# interacto.net
KiCad netlist of a schematic drawn in EAGLE
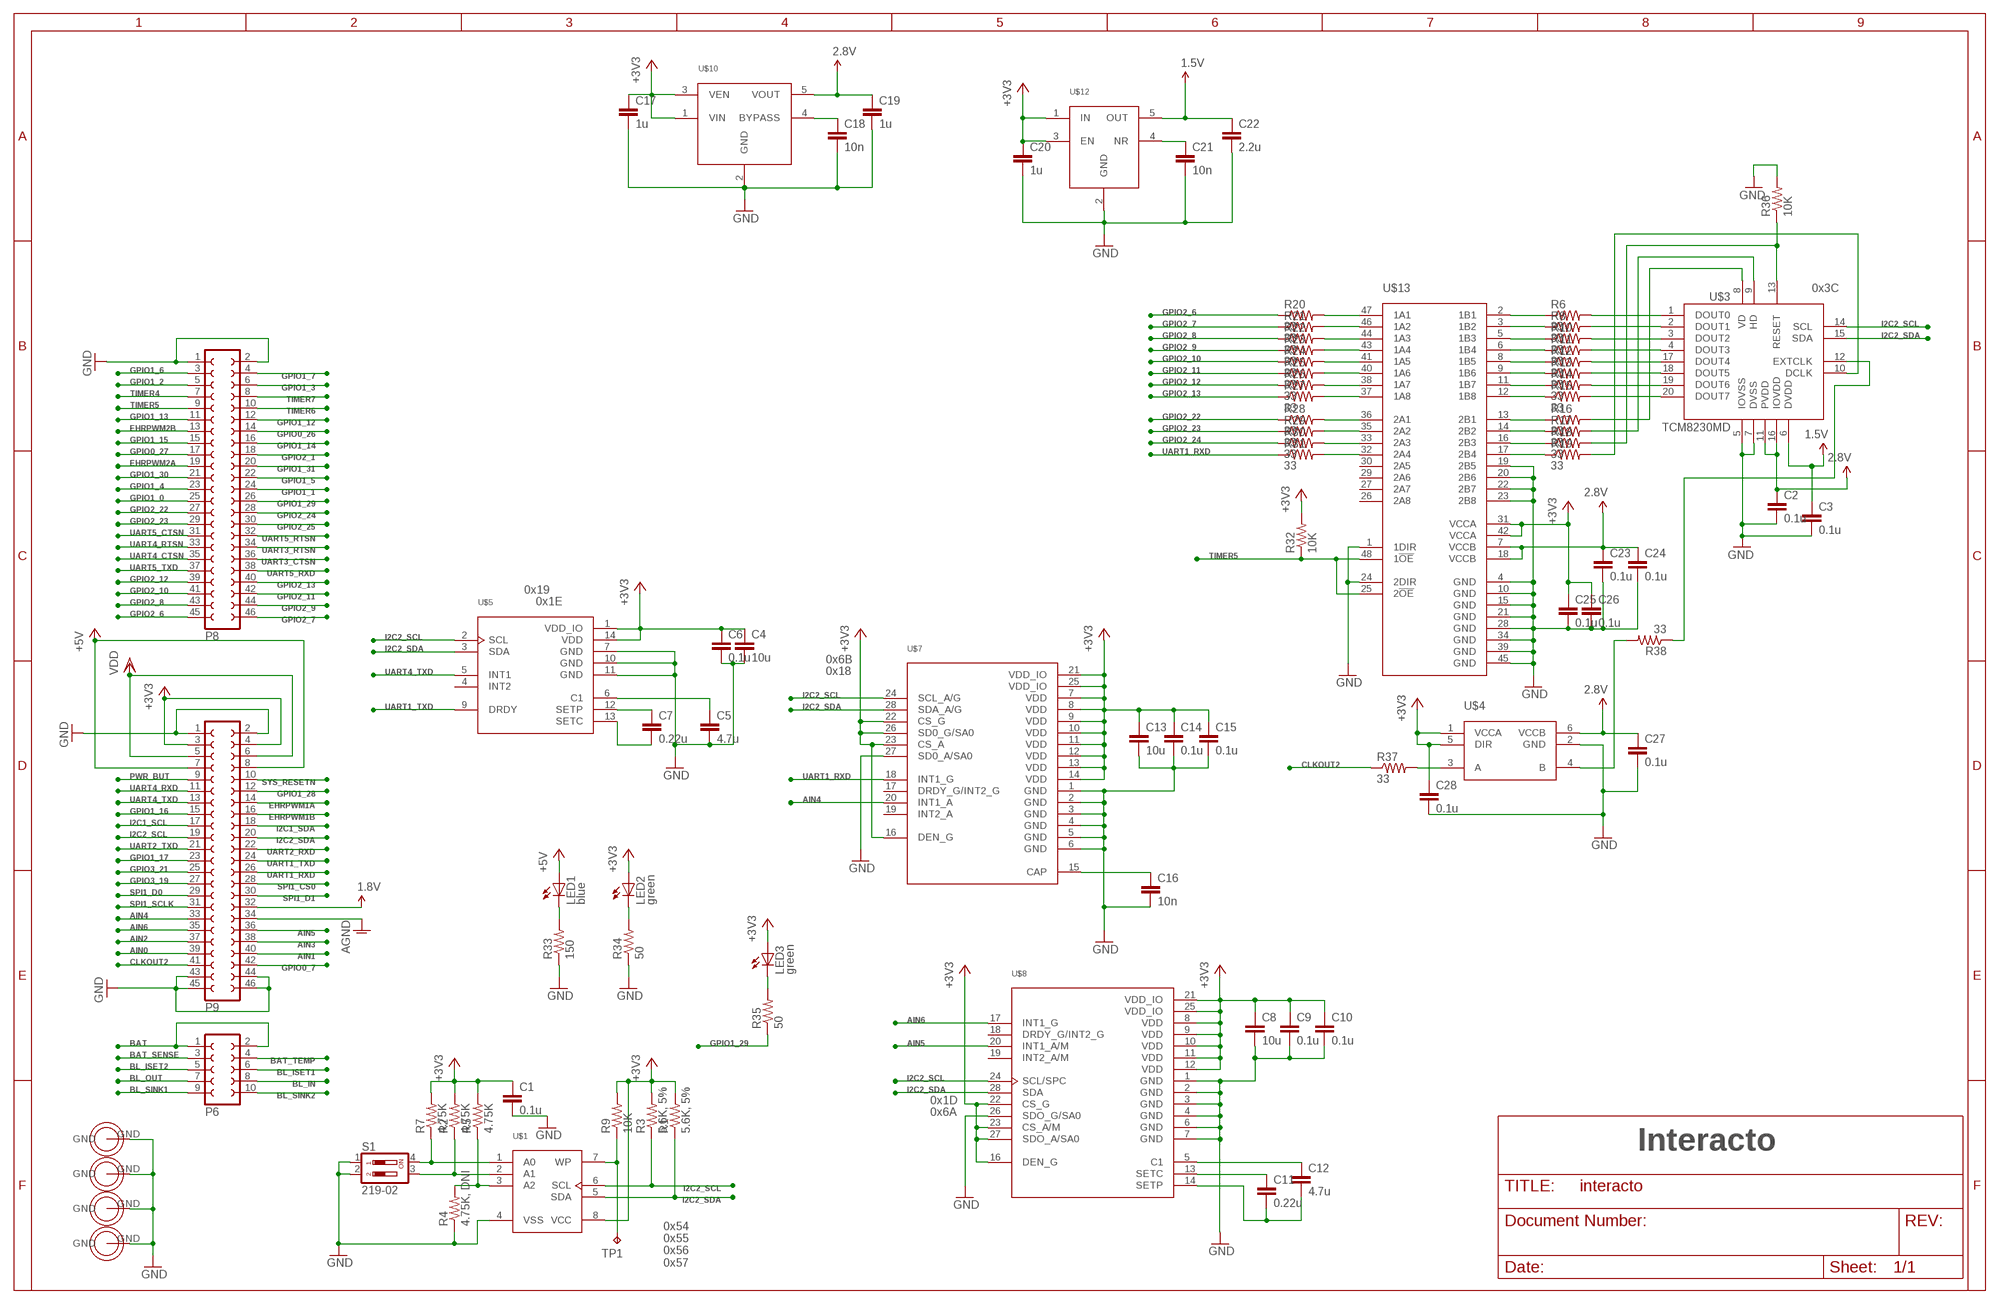
[diagram p0: schematic, sheet 1]

(export (version "E")
  (design (tool "Eeschema 10.0.6"))
  (components
    (comp (ref "C1")
      (value "0.1u")
      (footprint "eagle-import:C0603")
      (fields (field (name "MPN") "VJ0603V104ZXXCW1BC"))
      (libsource (lib "eagle-import") (part "C-EUC0603"))
    )
    (comp (ref "C2")
      (value "0.1u")
      (footprint "eagle-import:C0603")
      (fields (field (name "MPN") "VJ0603V104ZXXCW1BC"))
      (libsource (lib "eagle-import") (part "C-EUC0603"))
    )
    (comp (ref "C3")
      (value "0.1u")
      (footprint "eagle-import:C0603")
      (fields (field (name "MPN") "VJ0603V104ZXXCW1BC"))
      (libsource (lib "eagle-import") (part "C-EUC0603"))
    )
    (comp (ref "C4")
      (value "10u")
      (footprint "eagle-import:C0603")
      (fields (field (name "MPN") "LMK107BBJ106MALT"))
      (libsource (lib "eagle-import") (part "C-EUC0603"))
    )
    (comp (ref "C5")
      (value "4.7u")
      (footprint "eagle-import:C0603")
      (fields (field (name "MPN") "GRM188F51A475ZE20J"))
      (libsource (lib "eagle-import") (part "C-EUC0603"))
    )
    (comp (ref "C6")
      (value "0.1u")
      (footprint "eagle-import:C0603")
      (fields (field (name "MPN") "VJ0603V104ZXXCW1BC"))
      (libsource (lib "eagle-import") (part "C-EUC0603"))
    )
    (comp (ref "C7")
      (value "0.22u")
      (footprint "eagle-import:C0603")
      (fields (field (name "MPN") "VJ0603V224MXJPW1BC"))
      (libsource (lib "eagle-import") (part "C-EUC0603"))
    )
    (comp (ref "C8")
      (value "10u")
      (footprint "eagle-import:C0603")
      (fields (field (name "MPN") "LMK107BBJ106MALT"))
      (libsource (lib "eagle-import") (part "C-EUC0603"))
    )
    (comp (ref "C9")
      (value "0.1u")
      (footprint "eagle-import:C0603")
      (fields (field (name "MPN") "VJ0603V104ZXXCW1BC"))
      (libsource (lib "eagle-import") (part "C-EUC0603"))
    )
    (comp (ref "C10")
      (value "0.1u")
      (footprint "eagle-import:C0603")
      (fields (field (name "MPN") "VJ0603V104ZXXCW1BC"))
      (libsource (lib "eagle-import") (part "C-EUC0603"))
    )
    (comp (ref "C11")
      (value "0.22u")
      (footprint "eagle-import:C0603")
      (fields (field (name "MPN") "VJ0603V224MXJPW1BC"))
      (libsource (lib "eagle-import") (part "C-EUC0603"))
    )
    (comp (ref "C12")
      (value "4.7u")
      (footprint "eagle-import:C0603")
      (fields (field (name "MPN") "GRM188F51A475ZE20J"))
      (libsource (lib "eagle-import") (part "C-EUC0603"))
    )
    (comp (ref "C13")
      (value "10u")
      (footprint "eagle-import:C0603")
      (fields (field (name "MPN") "LMK107BBJ106MALT"))
      (libsource (lib "eagle-import") (part "C-EUC0603"))
    )
    (comp (ref "C14")
      (value "0.1u")
      (footprint "eagle-import:C0603")
      (fields (field (name "MPN") "VJ0603V104ZXXCW1BC"))
      (libsource (lib "eagle-import") (part "C-EUC0603"))
    )
    (comp (ref "C15")
      (value "0.1u")
      (footprint "eagle-import:C0603")
      (fields (field (name "MPN") "VJ0603V104ZXXCW1BC"))
      (libsource (lib "eagle-import") (part "C-EUC0603"))
    )
    (comp (ref "C16")
      (value "10n")
      (footprint "eagle-import:C0603")
      (fields (field (name "MPN") "VJ0603Y103KXACW1BC"))
      (libsource (lib "eagle-import") (part "C-EUC0603"))
    )
    (comp (ref "C17")
      (value "1u")
      (footprint "eagle-import:C0603")
      (fields (field (name "MPN") "C1608X7R1C105K"))
      (libsource (lib "eagle-import") (part "C-EUC0603"))
    )
    (comp (ref "C18")
      (value "10n")
      (footprint "eagle-import:C0603")
      (fields (field (name "MPN") "VJ0603Y103KXACW1BC"))
      (libsource (lib "eagle-import") (part "C-EUC0603"))
    )
    (comp (ref "C19")
      (value "1u")
      (footprint "eagle-import:C0603")
      (fields (field (name "MPN") "C1608X7R1C105K"))
      (libsource (lib "eagle-import") (part "C-EUC0603"))
    )
    (comp (ref "C20")
      (value "1u")
      (footprint "eagle-import:C0603")
      (fields (field (name "MPN") "C1608X7R1C105K"))
      (libsource (lib "eagle-import") (part "C-EUC0603"))
    )
    (comp (ref "C21")
      (value "10n")
      (footprint "eagle-import:C0603")
      (fields (field (name "MPN") "VJ0603Y103KXACW1BC"))
      (libsource (lib "eagle-import") (part "C-EUC0603"))
    )
    (comp (ref "C22")
      (value "2.2u")
      (footprint "eagle-import:C0603")
      (fields (field (name "MPN") "C1608Y5V1C225Z"))
      (libsource (lib "eagle-import") (part "C-EUC0603"))
    )
    (comp (ref "C23")
      (value "0.1u")
      (footprint "eagle-import:C0603")
      (fields (field (name "MPN") "VJ0603V104ZXXCW1BC"))
      (libsource (lib "eagle-import") (part "C-EUC0603"))
    )
    (comp (ref "C24")
      (value "0.1u")
      (footprint "eagle-import:C0603")
      (fields (field (name "MPN") "VJ0603V104ZXXCW1BC"))
      (libsource (lib "eagle-import") (part "C-EUC0603"))
    )
    (comp (ref "C25")
      (value "0.1u")
      (footprint "eagle-import:C0603")
      (fields (field (name "MPN") "VJ0603V104ZXXCW1BC"))
      (libsource (lib "eagle-import") (part "C-EUC0603"))
    )
    (comp (ref "C26")
      (value "0.1u")
      (footprint "eagle-import:C0603")
      (fields (field (name "MPN") "VJ0603V104ZXXCW1BC"))
      (libsource (lib "eagle-import") (part "C-EUC0603"))
    )
    (comp (ref "C27")
      (value "0.1u")
      (footprint "eagle-import:C0603")
      (fields (field (name "MPN") "VJ0603V104ZXXCW1BC"))
      (libsource (lib "eagle-import") (part "C-EUC0603"))
    )
    (comp (ref "C28")
      (value "0.1u")
      (footprint "eagle-import:C0603")
      (fields (field (name "MPN") "VJ0603V104ZXXCW1BC"))
      (libsource (lib "eagle-import") (part "C-EUC0603"))
    )
    (comp (ref "H1")
      (value "HOLE")
      (footprint "eagle-import:HOLE")
      (libsource (lib "eagle-import") (part "HOLE"))
    )
    (comp (ref "H2")
      (value "HOLE")
      (footprint "eagle-import:HOLE")
      (libsource (lib "eagle-import") (part "HOLE"))
    )
    (comp (ref "H3")
      (value "HOLE")
      (footprint "eagle-import:HOLE")
      (libsource (lib "eagle-import") (part "HOLE"))
    )
    (comp (ref "H4")
      (value "HOLE")
      (footprint "eagle-import:HOLE")
      (libsource (lib "eagle-import") (part "HOLE"))
    )
    (comp (ref "LED1")
      (value "blue")
      (footprint "eagle-import:CHIPLED_0603")
      (fields (field (name "MPN") "HT-193NB-5589"))
      (libsource (lib "eagle-import") (part "LEDCHIPLED_0603"))
    )
    (comp (ref "LED2")
      (value "green")
      (footprint "eagle-import:CHIPLED_0603")
      (fields (field (name "MPN") "LG Q971-KN-1"))
      (libsource (lib "eagle-import") (part "LEDCHIPLED_0603"))
    )
    (comp (ref "LED3")
      (value "green")
      (footprint "eagle-import:CHIPLED_0603")
      (fields (field (name "MPN") "LG Q971-KN-1"))
      (libsource (lib "eagle-import") (part "LEDCHIPLED_0603"))
    )
    (comp (ref "P6")
      (value "FE05-2")
      (footprint "eagle-import:FE05-2")
      (fields (field (name "MPN") "SSHQ-105-D-10-GT-LF "))
      (libsource (lib "eagle-import") (part "FE05-2"))
    )
    (comp (ref "P8")
      (value "FE23-2")
      (footprint "eagle-import:FE23-2")
      (fields (field (name "MPN") "SSHQ-123-D-10-GT-LF "))
      (libsource (lib "eagle-import") (part "FE23-2"))
    )
    (comp (ref "P9")
      (value "FE23-2")
      (footprint "eagle-import:FE23-2")
      (fields (field (name "MPN") "SSHQ-123-D-10-GT-LF "))
      (libsource (lib "eagle-import") (part "FE23-2"))
    )
    (comp (ref "R1")
      (value "5.6K, 5%")
      (footprint "eagle-import:R0603")
      (fields (field (name "MPN") "RK73B1JTTDD562J"))
      (libsource (lib "eagle-import") (part "R-US_R0603"))
    )
    (comp (ref "R2")
      (value "4.75K")
      (footprint "eagle-import:R0603")
      (fields (field (name "MPN") "CR0603-FX-4751GLF"))
      (libsource (lib "eagle-import") (part "R-US_R0603"))
    )
    (comp (ref "R3")
      (value "5.6K, 5%")
      (footprint "eagle-import:R0603")
      (fields (field (name "MPN") "RK73B1JTTDD562J"))
      (libsource (lib "eagle-import") (part "R-US_R0603"))
    )
    (comp (ref "R4")
      (value "4.75K, DNI")
      (footprint "eagle-import:R0603")
      (fields (field (name "MPN") "CR0603-FX-4751GLF"))
      (libsource (lib "eagle-import") (part "R-US_R0603"))
    )
    (comp (ref "R5")
      (value "4.75K")
      (footprint "eagle-import:R0603")
      (fields (field (name "MPN") "CR0603-FX-4751GLF"))
      (libsource (lib "eagle-import") (part "R-US_R0603"))
    )
    (comp (ref "R6")
      (value "33")
      (footprint "eagle-import:R0402")
      (fields (field (name "MPN") "CR0402-JW-330GLF"))
      (libsource (lib "eagle-import") (part "R-US_R0402"))
    )
    (comp (ref "R7")
      (value "4.75K")
      (footprint "eagle-import:R0603")
      (fields (field (name "MPN") "CR0603-FX-4751GLF"))
      (libsource (lib "eagle-import") (part "R-US_R0603"))
    )
    (comp (ref "R8")
      (value "33")
      (footprint "eagle-import:R0402")
      (fields (field (name "MPN") "CR0402-JW-330GLF"))
      (libsource (lib "eagle-import") (part "R-US_R0402"))
    )
    (comp (ref "R9")
      (value "10K")
      (footprint "eagle-import:R0603")
      (fields (field (name "MPN") "WR06X1002FTL"))
      (libsource (lib "eagle-import") (part "R-US_R0603"))
    )
    (comp (ref "R10")
      (value "33")
      (footprint "eagle-import:R0402")
      (fields (field (name "MPN") "CR0402-JW-330GLF"))
      (libsource (lib "eagle-import") (part "R-US_R0402"))
    )
    (comp (ref "R11")
      (value "33")
      (footprint "eagle-import:R0402")
      (fields (field (name "MPN") "CR0402-JW-330GLF"))
      (libsource (lib "eagle-import") (part "R-US_R0402"))
    )
    (comp (ref "R12")
      (value "33")
      (footprint "eagle-import:R0402")
      (fields (field (name "MPN") "CR0402-JW-330GLF"))
      (libsource (lib "eagle-import") (part "R-US_R0402"))
    )
    (comp (ref "R13")
      (value "33")
      (footprint "eagle-import:R0402")
      (fields (field (name "MPN") "CR0402-JW-330GLF"))
      (libsource (lib "eagle-import") (part "R-US_R0402"))
    )
    (comp (ref "R14")
      (value "33")
      (footprint "eagle-import:R0402")
      (fields (field (name "MPN") "CR0402-JW-330GLF"))
      (libsource (lib "eagle-import") (part "R-US_R0402"))
    )
    (comp (ref "R15")
      (value "33")
      (footprint "eagle-import:R0402")
      (fields (field (name "MPN") "CR0402-JW-330GLF"))
      (libsource (lib "eagle-import") (part "R-US_R0402"))
    )
    (comp (ref "R16")
      (value "33")
      (footprint "eagle-import:R0402")
      (fields (field (name "MPN") "CR0402-JW-330GLF"))
      (libsource (lib "eagle-import") (part "R-US_R0402"))
    )
    (comp (ref "R17")
      (value "33")
      (footprint "eagle-import:R0402")
      (fields (field (name "MPN") "CR0402-JW-330GLF"))
      (libsource (lib "eagle-import") (part "R-US_R0402"))
    )
    (comp (ref "R18")
      (value "33")
      (footprint "eagle-import:R0402")
      (fields (field (name "MPN") "CR0402-JW-330GLF"))
      (libsource (lib "eagle-import") (part "R-US_R0402"))
    )
    (comp (ref "R19")
      (value "33")
      (footprint "eagle-import:R0402")
      (fields (field (name "MPN") "CR0402-JW-330GLF"))
      (libsource (lib "eagle-import") (part "R-US_R0402"))
    )
    (comp (ref "R20")
      (value "33")
      (footprint "eagle-import:R0402")
      (fields (field (name "MPN") "CR0402-JW-330GLF"))
      (libsource (lib "eagle-import") (part "R-US_R0402"))
    )
    (comp (ref "R21")
      (value "33")
      (footprint "eagle-import:R0402")
      (fields (field (name "MPN") "CR0402-JW-330GLF"))
      (libsource (lib "eagle-import") (part "R-US_R0402"))
    )
    (comp (ref "R22")
      (value "33")
      (footprint "eagle-import:R0402")
      (fields (field (name "MPN") "CR0402-JW-330GLF"))
      (libsource (lib "eagle-import") (part "R-US_R0402"))
    )
    (comp (ref "R23")
      (value "33")
      (footprint "eagle-import:R0402")
      (fields (field (name "MPN") "CR0402-JW-330GLF"))
      (libsource (lib "eagle-import") (part "R-US_R0402"))
    )
    (comp (ref "R24")
      (value "33")
      (footprint "eagle-import:R0402")
      (libsource (lib "eagle-import") (part "R-US_R0402"))
    )
    (comp (ref "R25")
      (value "33")
      (footprint "eagle-import:R0402")
      (fields (field (name "MPN") "CR0402-JW-330GLF"))
      (libsource (lib "eagle-import") (part "R-US_R0402"))
    )
    (comp (ref "R26")
      (value "33")
      (footprint "eagle-import:R0402")
      (fields (field (name "MPN") "CR0402-JW-330GLF"))
      (libsource (lib "eagle-import") (part "R-US_R0402"))
    )
    (comp (ref "R27")
      (value "33")
      (footprint "eagle-import:R0402")
      (fields (field (name "MPN") "CR0402-JW-330GLF"))
      (libsource (lib "eagle-import") (part "R-US_R0402"))
    )
    (comp (ref "R28")
      (value "33")
      (footprint "eagle-import:R0402")
      (fields (field (name "MPN") "CR0402-JW-330GLF"))
      (libsource (lib "eagle-import") (part "R-US_R0402"))
    )
    (comp (ref "R29")
      (value "33")
      (footprint "eagle-import:R0402")
      (fields (field (name "MPN") "CR0402-JW-330GLF"))
      (libsource (lib "eagle-import") (part "R-US_R0402"))
    )
    (comp (ref "R30")
      (value "33")
      (footprint "eagle-import:R0402")
      (fields (field (name "MPN") "CR0402-JW-330GLF"))
      (libsource (lib "eagle-import") (part "R-US_R0402"))
    )
    (comp (ref "R31")
      (value "33")
      (footprint "eagle-import:R0402")
      (fields (field (name "MPN") "CR0402-JW-330GLF"))
      (libsource (lib "eagle-import") (part "R-US_R0402"))
    )
    (comp (ref "R32")
      (value "10K")
      (footprint "eagle-import:R0402")
      (fields (field (name "MPN") "WR06X1002FTL"))
      (libsource (lib "eagle-import") (part "R-US_R0402"))
    )
    (comp (ref "R33")
      (value "150")
      (footprint "eagle-import:R0603")
      (fields (field (name "MPN") "302-150-RC"))
      (libsource (lib "eagle-import") (part "R-US_R0603"))
    )
    (comp (ref "R34")
      (value "50")
      (footprint "eagle-import:R0603")
      (fields (field (name "MPN") "302-49.9-RC"))
      (libsource (lib "eagle-import") (part "R-US_R0603"))
    )
    (comp (ref "R35")
      (value "50")
      (footprint "eagle-import:R0603")
      (fields (field (name "MPN") "302-49.9-RC"))
      (libsource (lib "eagle-import") (part "R-US_R0603"))
    )
    (comp (ref "R36")
      (value "10K")
      (footprint "eagle-import:R0402")
      (fields (field (name "MPN") "WR06X1002FTL"))
      (libsource (lib "eagle-import") (part "R-US_R0402"))
    )
    (comp (ref "R37")
      (value "33")
      (footprint "eagle-import:R0402")
      (fields (field (name "MPN") "CR0402-JW-330GLF"))
      (libsource (lib "eagle-import") (part "R-US_R0402"))
    )
    (comp (ref "R38")
      (value "33")
      (footprint "eagle-import:R0402")
      (fields (field (name "MPN") "CR0402-JW-330GLF"))
      (libsource (lib "eagle-import") (part "R-US_R0402"))
    )
    (comp (ref "S1")
      (value "219-02")
      (footprint "eagle-import:CTS-219-02")
      (fields (field (name "MPN") "219-2MST"))
      (libsource (lib "eagle-import") (part "219-02"))
    )
    (comp (ref "TP1")
      (value "TPB2,54")
      (footprint "eagle-import:B2,54")
      (libsource (lib "eagle-import") (part "TPB2,54"))
    )
    (comp (ref "U$1")
      (value "CAT24C256")
      (footprint "eagle-import:SOIC8")
      (fields (field (name "MPN") "CAT24C256WI-GT3"))
      (libsource (lib "eagle-import") (part "CAT24C256"))
    )
    (comp (ref "U$3")
      (value "TCM8230MD")
      (footprint "eagle-import:TCM8230MD")
      (libsource (lib "eagle-import") (part "TCM8230MD"))
    )
    (comp (ref "U$4")
      (value "SN74LVC1T45")
      (footprint "eagle-import:SOT23-6")
      (fields (field (name "MPN") "SN74LVC1T45DBVR"))
      (libsource (lib "eagle-import") (part "SN74LVC1T45"))
    )
    (comp (ref "U$5")
      (value "LSM303DLHC")
      (footprint "eagle-import:LGA14")
      (libsource (lib "eagle-import") (part "LSM303DLHC"))
    )
    (comp (ref "U$7")
      (value "LSM330DLC")
      (footprint "eagle-import:LGA28-4X5")
      (libsource (lib "eagle-import") (part "LSM330DLC"))
    )
    (comp (ref "U$8")
      (value "LSM333D")
      (footprint "eagle-import:LGA28")
      (libsource (lib "eagle-import") (part "LSM333D"))
    )
    (comp (ref "U$10")
      (value "LP3985")
      (footprint "eagle-import:SOT23-5")
      (fields (field (name "MPN") "LP3985IM5-2.8/NOPB"))
      (libsource (lib "eagle-import") (part "LP3985"))
    )
    (comp (ref "U$12")
      (value "TPS799XX")
      (footprint "eagle-import:SOT23-5")
      (fields (field (name "MPN") "TPS79915DDCR"))
      (libsource (lib "eagle-import") (part "TPS799XX"))
    )
    (comp (ref "U$13")
      (value "SN74LVCH16T245")
      (footprint "eagle-import:TSSOP48")
      (fields (field (name "MPN") "SN74LVCH16T245DGGR"))
      (libsource (lib "eagle-import") (part "SN74LVCH16T245"))
    )
  )
  (nets
    (net (code "1") (name "+3V3") (class "Default")
      (node (ref "C1") (pin "1") (pinfunction "1_1") (pintype "passive"))
      (node (ref "C10") (pin "1") (pinfunction "1_1") (pintype "passive"))
      (node (ref "C13") (pin "1") (pinfunction "1_1") (pintype "passive"))
      (node (ref "C14") (pin "1") (pinfunction "1_1") (pintype "passive"))
      (node (ref "C15") (pin "1") (pinfunction "1_1") (pintype "passive"))
      (node (ref "C17") (pin "1") (pinfunction "1_1") (pintype "passive"))
      (node (ref "C20") (pin "1") (pinfunction "1_1") (pintype "passive"))
      (node (ref "C25") (pin "1") (pinfunction "1_1") (pintype "passive"))
      (node (ref "C26") (pin "1") (pinfunction "1_1") (pintype "passive"))
      (node (ref "C28") (pin "1") (pinfunction "1_1") (pintype "passive"))
      (node (ref "C4") (pin "1") (pinfunction "1_1") (pintype "passive"))
      (node (ref "C6") (pin "1") (pinfunction "1_1") (pintype "passive"))
      (node (ref "C8") (pin "1") (pinfunction "1_1") (pintype "passive"))
      (node (ref "C9") (pin "1") (pinfunction "1_1") (pintype "passive"))
      (node (ref "LED2") (pin "A") (pinfunction "A_A") (pintype "passive"))
      (node (ref "LED3") (pin "A") (pinfunction "A_A") (pintype "passive"))
      (node (ref "P9") (pin "3") (pinfunction "3_3") (pintype "passive"))
      (node (ref "P9") (pin "4") (pinfunction "4_4") (pintype "passive"))
      (node (ref "R1") (pin "2") (pinfunction "2_2") (pintype "passive"))
      (node (ref "R2") (pin "2") (pinfunction "2_2") (pintype "passive"))
      (node (ref "R3") (pin "2") (pinfunction "2_2") (pintype "passive"))
      (node (ref "R32") (pin "2") (pinfunction "2_2") (pintype "passive"))
      (node (ref "R5") (pin "2") (pinfunction "2_2") (pintype "passive"))
      (node (ref "R7") (pin "2") (pinfunction "2_2") (pintype "passive"))
      (node (ref "R9") (pin "2") (pinfunction "2_2") (pintype "passive"))
      (node (ref "U$1") (pin "8") (pinfunction "VCC_8") (pintype "power_in"))
      (node (ref "U$10") (pin "1") (pinfunction "VIN_1") (pintype "power_in"))
      (node (ref "U$10") (pin "3") (pinfunction "VEN_3") (pintype "input"))
      (node (ref "U$12") (pin "1") (pinfunction "IN_1") (pintype "power_in"))
      (node (ref "U$12") (pin "3") (pinfunction "EN_3") (pintype "input"))
      (node (ref "U$13") (pin "31") (pinfunction "VCCA_31") (pintype "power_in"))
      (node (ref "U$13") (pin "42") (pinfunction "VCCA_42") (pintype "power_in"))
      (node (ref "U$4") (pin "1") (pinfunction "VCCA_1") (pintype "power_in"))
      (node (ref "U$4") (pin "5") (pinfunction "DIR_5") (pintype "input"))
      (node (ref "U$5") (pin "1") (pinfunction "VDD_IO_1") (pintype "power_in"))
      (node (ref "U$5") (pin "14") (pinfunction "VDD_14") (pintype "power_in"))
      (node (ref "U$7") (pin "10") (pinfunction "VDD_10") (pintype "power_in"))
      (node (ref "U$7") (pin "11") (pinfunction "VDD_11") (pintype "power_in"))
      (node (ref "U$7") (pin "12") (pinfunction "VDD_12") (pintype "power_in"))
      (node (ref "U$7") (pin "13") (pinfunction "VDD_13") (pintype "power_in"))
      (node (ref "U$7") (pin "14") (pinfunction "VDD_14") (pintype "power_in"))
      (node (ref "U$7") (pin "16") (pinfunction "DEN_G_16") (pintype "input"))
      (node (ref "U$7") (pin "21") (pinfunction "VDD_IO_21") (pintype "power_in"))
      (node (ref "U$7") (pin "22") (pinfunction "CS_G_22") (pintype "input"))
      (node (ref "U$7") (pin "23") (pinfunction "CS_A_23") (pintype "input"))
      (node (ref "U$7") (pin "25") (pinfunction "VDD_IO_25") (pintype "power_in"))
      (node (ref "U$7") (pin "26") (pinfunction "SD0_G/SA0_26") (pintype "bidirectional"))
      (node (ref "U$7") (pin "7") (pinfunction "VDD_7") (pintype "power_in"))
      (node (ref "U$7") (pin "8") (pinfunction "VDD_8") (pintype "power_in"))
      (node (ref "U$7") (pin "9") (pinfunction "VDD_9") (pintype "power_in"))
      (node (ref "U$8") (pin "10") (pinfunction "VDD_10") (pintype "power_in"))
      (node (ref "U$8") (pin "11") (pinfunction "VDD_11") (pintype "power_in"))
      (node (ref "U$8") (pin "12") (pinfunction "VDD_12") (pintype "power_in"))
      (node (ref "U$8") (pin "16") (pinfunction "DEN_G_16") (pintype "input"))
      (node (ref "U$8") (pin "21") (pinfunction "VDD_IO_21") (pintype "power_in"))
      (node (ref "U$8") (pin "22") (pinfunction "CS_G_22") (pintype "input"))
      (node (ref "U$8") (pin "23") (pinfunction "CS_A/M_23") (pintype "input"))
      (node (ref "U$8") (pin "25") (pinfunction "VDD_IO_25") (pintype "power_in"))
      (node (ref "U$8") (pin "27") (pinfunction "SDO_A/SA0_27") (pintype "bidirectional"))
      (node (ref "U$8") (pin "8") (pinfunction "VDD_8") (pintype "power_in"))
      (node (ref "U$8") (pin "9") (pinfunction "VDD_9") (pintype "power_in"))
    )
    (net (code "2") (name "+5V") (class "Default")
      (node (ref "LED1") (pin "A") (pinfunction "A_A") (pintype "passive"))
      (node (ref "P9") (pin "7") (pinfunction "7_7") (pintype "passive"))
      (node (ref "P9") (pin "8") (pinfunction "8_8") (pintype "passive"))
    )
    (net (code "3") (name "/AIN0") (class "Default")
      (node (ref "P9") (pin "39") (pinfunction "39_39") (pintype "passive"))
    )
    (net (code "4") (name "/AIN1") (class "Default")
      (node (ref "P9") (pin "40") (pinfunction "40_40") (pintype "passive"))
    )
    (net (code "5") (name "/AIN2") (class "Default")
      (node (ref "P9") (pin "37") (pinfunction "37_37") (pintype "passive"))
    )
    (net (code "6") (name "/AIN3") (class "Default")
      (node (ref "P9") (pin "38") (pinfunction "38_38") (pintype "passive"))
    )
    (net (code "7") (name "/AIN4") (class "Default")
      (node (ref "P9") (pin "33") (pinfunction "33_33") (pintype "passive"))
      (node (ref "U$7") (pin "20") (pinfunction "INT1_A_20") (pintype "output"))
    )
    (net (code "8") (name "/AIN5") (class "Default")
      (node (ref "P9") (pin "36") (pinfunction "36_36") (pintype "passive"))
      (node (ref "U$8") (pin "20") (pinfunction "INT1_A/M_20") (pintype "output"))
    )
    (net (code "9") (name "/AIN6") (class "Default")
      (node (ref "P9") (pin "35") (pinfunction "35_35") (pintype "passive"))
      (node (ref "U$8") (pin "17") (pinfunction "INT1_G_17") (pintype "output"))
    )
    (net (code "10") (name "/BAT") (class "Default")
      (node (ref "P6") (pin "1") (pinfunction "1_1") (pintype "passive"))
      (node (ref "P6") (pin "2") (pinfunction "2_2") (pintype "passive"))
    )
    (net (code "11") (name "/BAT_SENSE") (class "Default")
      (node (ref "P6") (pin "3") (pinfunction "3_3") (pintype "passive"))
    )
    (net (code "12") (name "/BAT_TEMP") (class "Default")
      (node (ref "P6") (pin "4") (pinfunction "4_4") (pintype "passive"))
    )
    (net (code "13") (name "/BL_IN") (class "Default")
      (node (ref "P6") (pin "8") (pinfunction "8_8") (pintype "passive"))
    )
    (net (code "14") (name "/BL_ISET1") (class "Default")
      (node (ref "P6") (pin "6") (pinfunction "6_6") (pintype "passive"))
    )
    (net (code "15") (name "/BL_ISET2") (class "Default")
      (node (ref "P6") (pin "5") (pinfunction "5_5") (pintype "passive"))
    )
    (net (code "16") (name "/BL_OUT") (class "Default")
      (node (ref "P6") (pin "7") (pinfunction "7_7") (pintype "passive"))
    )
    (net (code "17") (name "/BL_SINK1") (class "Default")
      (node (ref "P6") (pin "9") (pinfunction "9_9") (pintype "passive"))
    )
    (net (code "18") (name "/BL_SINK2") (class "Default")
      (node (ref "P6") (pin "10") (pinfunction "10_10") (pintype "passive"))
    )
    (net (code "19") (name "/CLKOUT2") (class "Default")
      (node (ref "P9") (pin "41") (pinfunction "41_41") (pintype "passive"))
      (node (ref "R37") (pin "1") (pinfunction "1_1") (pintype "passive"))
    )
    (net (code "20") (name "/EHRPWM1A") (class "Default")
      (node (ref "P9") (pin "14") (pinfunction "14_14") (pintype "passive"))
    )
    (net (code "21") (name "/EHRPWM1B") (class "Default")
      (node (ref "P9") (pin "16") (pinfunction "16_16") (pintype "passive"))
    )
    (net (code "22") (name "/EHRPWM2A") (class "Default")
      (node (ref "P8") (pin "19") (pinfunction "19_19") (pintype "passive"))
    )
    (net (code "23") (name "/EHRPWM2B") (class "Default")
      (node (ref "P8") (pin "13") (pinfunction "13_13") (pintype "passive"))
    )
    (net (code "24") (name "/GPIO0_7") (class "Default")
      (node (ref "P9") (pin "42") (pinfunction "42_42") (pintype "passive"))
    )
    (net (code "25") (name "/GPIO0_26") (class "Default")
      (node (ref "P8") (pin "14") (pinfunction "14_14") (pintype "passive"))
    )
    (net (code "26") (name "/GPIO0_27") (class "Default")
      (node (ref "P8") (pin "17") (pinfunction "17_17") (pintype "passive"))
    )
    (net (code "27") (name "/GPIO1_0") (class "Default")
      (node (ref "P8") (pin "25") (pinfunction "25_25") (pintype "passive"))
    )
    (net (code "28") (name "/GPIO1_1") (class "Default")
      (node (ref "P8") (pin "24") (pinfunction "24_24") (pintype "passive"))
    )
    (net (code "29") (name "/GPIO1_2") (class "Default")
      (node (ref "P8") (pin "5") (pinfunction "5_5") (pintype "passive"))
    )
    (net (code "30") (name "/GPIO1_3") (class "Default")
      (node (ref "P8") (pin "6") (pinfunction "6_6") (pintype "passive"))
    )
    (net (code "31") (name "/GPIO1_4") (class "Default")
      (node (ref "P8") (pin "23") (pinfunction "23_23") (pintype "passive"))
    )
    (net (code "32") (name "/GPIO1_5") (class "Default")
      (node (ref "P8") (pin "22") (pinfunction "22_22") (pintype "passive"))
    )
    (net (code "33") (name "/GPIO1_6") (class "Default")
      (node (ref "P8") (pin "3") (pinfunction "3_3") (pintype "passive"))
    )
    (net (code "34") (name "/GPIO1_7") (class "Default")
      (node (ref "P8") (pin "4") (pinfunction "4_4") (pintype "passive"))
    )
    (net (code "35") (name "/GPIO1_12") (class "Default")
      (node (ref "P8") (pin "12") (pinfunction "12_12") (pintype "passive"))
    )
    (net (code "36") (name "/GPIO1_13") (class "Default")
      (node (ref "P8") (pin "11") (pinfunction "11_11") (pintype "passive"))
    )
    (net (code "37") (name "/GPIO1_14") (class "Default")
      (node (ref "P8") (pin "16") (pinfunction "16_16") (pintype "passive"))
    )
    (net (code "38") (name "/GPIO1_15") (class "Default")
      (node (ref "P8") (pin "15") (pinfunction "15_15") (pintype "passive"))
    )
    (net (code "39") (name "/GPIO1_16") (class "Default")
      (node (ref "P9") (pin "15") (pinfunction "15_15") (pintype "passive"))
    )
    (net (code "40") (name "/GPIO1_17") (class "Default")
      (node (ref "P9") (pin "23") (pinfunction "23_23") (pintype "passive"))
    )
    (net (code "41") (name "/GPIO1_28") (class "Default")
      (node (ref "P9") (pin "12") (pinfunction "12_12") (pintype "passive"))
    )
    (net (code "42") (name "/GPIO1_29") (class "Default")
      (node (ref "P8") (pin "26") (pinfunction "26_26") (pintype "passive"))
      (node (ref "R35") (pin "1") (pinfunction "1_1") (pintype "passive"))
    )
    (net (code "43") (name "/GPIO1_30") (class "Default")
      (node (ref "P8") (pin "21") (pinfunction "21_21") (pintype "passive"))
    )
    (net (code "44") (name "/GPIO1_31") (class "Default")
      (node (ref "P8") (pin "20") (pinfunction "20_20") (pintype "passive"))
    )
    (net (code "45") (name "/GPIO2_1") (class "Default")
      (node (ref "P8") (pin "18") (pinfunction "18_18") (pintype "passive"))
    )
    (net (code "46") (name "/GPIO2_6") (class "Default")
      (node (ref "P8") (pin "45") (pinfunction "45_45") (pintype "passive"))
      (node (ref "R20") (pin "1") (pinfunction "1_1") (pintype "passive"))
    )
    (net (code "47") (name "/GPIO2_7") (class "Default")
      (node (ref "P8") (pin "46") (pinfunction "46_46") (pintype "passive"))
      (node (ref "R21") (pin "1") (pinfunction "1_1") (pintype "passive"))
    )
    (net (code "48") (name "/GPIO2_8") (class "Default")
      (node (ref "P8") (pin "43") (pinfunction "43_43") (pintype "passive"))
      (node (ref "R22") (pin "1") (pinfunction "1_1") (pintype "passive"))
    )
    (net (code "49") (name "/GPIO2_9") (class "Default")
      (node (ref "P8") (pin "44") (pinfunction "44_44") (pintype "passive"))
      (node (ref "R23") (pin "1") (pinfunction "1_1") (pintype "passive"))
    )
    (net (code "50") (name "/GPIO2_10") (class "Default")
      (node (ref "P8") (pin "41") (pinfunction "41_41") (pintype "passive"))
      (node (ref "R24") (pin "1") (pinfunction "1_1") (pintype "passive"))
    )
    (net (code "51") (name "/GPIO2_11") (class "Default")
      (node (ref "P8") (pin "42") (pinfunction "42_42") (pintype "passive"))
      (node (ref "R25") (pin "1") (pinfunction "1_1") (pintype "passive"))
    )
    (net (code "52") (name "/GPIO2_12") (class "Default")
      (node (ref "P8") (pin "39") (pinfunction "39_39") (pintype "passive"))
      (node (ref "R26") (pin "1") (pinfunction "1_1") (pintype "passive"))
    )
    (net (code "53") (name "/GPIO2_13") (class "Default")
      (node (ref "P8") (pin "40") (pinfunction "40_40") (pintype "passive"))
      (node (ref "R27") (pin "1") (pinfunction "1_1") (pintype "passive"))
    )
    (net (code "54") (name "/GPIO2_22") (class "Default")
      (node (ref "P8") (pin "27") (pinfunction "27_27") (pintype "passive"))
      (node (ref "R28") (pin "1") (pinfunction "1_1") (pintype "passive"))
    )
    (net (code "55") (name "/GPIO2_23") (class "Default")
      (node (ref "P8") (pin "29") (pinfunction "29_29") (pintype "passive"))
      (node (ref "R29") (pin "1") (pinfunction "1_1") (pintype "passive"))
    )
    (net (code "56") (name "/GPIO2_24") (class "Default")
      (node (ref "P8") (pin "28") (pinfunction "28_28") (pintype "passive"))
      (node (ref "R30") (pin "1") (pinfunction "1_1") (pintype "passive"))
    )
    (net (code "57") (name "/GPIO2_25") (class "Default")
      (node (ref "P8") (pin "30") (pinfunction "30_30") (pintype "passive"))
    )
    (net (code "58") (name "/GPIO3_19") (class "Default")
      (node (ref "P9") (pin "27") (pinfunction "27_27") (pintype "passive"))
    )
    (net (code "59") (name "/GPIO3_21") (class "Default")
      (node (ref "P9") (pin "25") (pinfunction "25_25") (pintype "passive"))
    )
    (net (code "60") (name "/I2C1_SCL") (class "Default")
      (node (ref "P9") (pin "17") (pinfunction "17_17") (pintype "passive"))
    )
    (net (code "61") (name "/I2C1_SDA") (class "Default")
      (node (ref "P9") (pin "18") (pinfunction "18_18") (pintype "passive"))
    )
    (net (code "62") (name "/I2C2_SCL") (class "Default")
      (node (ref "P9") (pin "19") (pinfunction "19_19") (pintype "passive"))
      (node (ref "R3") (pin "1") (pinfunction "1_1") (pintype "passive"))
      (node (ref "U$1") (pin "6") (pinfunction "SCL_6") (pintype "open_collector"))
      (node (ref "U$3") (pin "14") (pinfunction "SCL_14") (pintype "bidirectional"))
      (node (ref "U$5") (pin "2") (pinfunction "SCL_2") (pintype "open_collector"))
      (node (ref "U$7") (pin "24") (pinfunction "SCL_A/G_24") (pintype "open_collector"))
      (node (ref "U$8") (pin "24") (pinfunction "SCL/SPC_24") (pintype "open_collector"))
    )
    (net (code "63") (name "/I2C2_SDA") (class "Default")
      (node (ref "P9") (pin "20") (pinfunction "20_20") (pintype "passive"))
      (node (ref "R1") (pin "1") (pinfunction "1_1") (pintype "passive"))
      (node (ref "U$1") (pin "5") (pinfunction "SDA_5") (pintype "open_collector"))
      (node (ref "U$3") (pin "15") (pinfunction "SDA_15") (pintype "bidirectional"))
      (node (ref "U$5") (pin "3") (pinfunction "SDA_3") (pintype "open_collector"))
      (node (ref "U$7") (pin "28") (pinfunction "SDA_A/G_28") (pintype "open_collector"))
      (node (ref "U$8") (pin "28") (pinfunction "SDA_28") (pintype "open_collector"))
    )
    (net (code "64") (name "/PWR_BUT") (class "Default")
      (node (ref "P9") (pin "9") (pinfunction "9_9") (pintype "passive"))
    )
    (net (code "65") (name "/SPI1_CS0") (class "Default")
      (node (ref "P9") (pin "28") (pinfunction "28_28") (pintype "passive"))
    )
    (net (code "66") (name "/SPI1_D0") (class "Default")
      (node (ref "P9") (pin "29") (pinfunction "29_29") (pintype "passive"))
    )
    (net (code "67") (name "/SPI1_D1") (class "Default")
      (node (ref "P9") (pin "30") (pinfunction "30_30") (pintype "passive"))
    )
    (net (code "68") (name "/SPI1_SCLK") (class "Default")
      (node (ref "P9") (pin "31") (pinfunction "31_31") (pintype "passive"))
    )
    (net (code "69") (name "/SYS_RESETN") (class "Default")
      (node (ref "P9") (pin "10") (pinfunction "10_10") (pintype "passive"))
    )
    (net (code "70") (name "/TIMER4") (class "Default")
      (node (ref "P8") (pin "7") (pinfunction "7_7") (pintype "passive"))
    )
    (net (code "71") (name "/TIMER5") (class "Default")
      (node (ref "P8") (pin "9") (pinfunction "9_9") (pintype "passive"))
      (node (ref "R32") (pin "1") (pinfunction "1_1") (pintype "passive"))
      (node (ref "U$13") (pin "25") (pinfunction "2~{OE}_25") (pintype "input"))
      (node (ref "U$13") (pin "48") (pinfunction "1~{OE}_48") (pintype "input"))
    )
    (net (code "72") (name "/TIMER6") (class "Default")
      (node (ref "P8") (pin "10") (pinfunction "10_10") (pintype "passive"))
    )
    (net (code "73") (name "/TIMER7") (class "Default")
      (node (ref "P8") (pin "8") (pinfunction "8_8") (pintype "passive"))
    )
    (net (code "74") (name "/UART1_RXD") (class "Default")
      (node (ref "P9") (pin "26") (pinfunction "26_26") (pintype "passive"))
      (node (ref "R31") (pin "1") (pinfunction "1_1") (pintype "passive"))
      (node (ref "U$7") (pin "18") (pinfunction "INT1_G_18") (pintype "output"))
    )
    (net (code "75") (name "/UART1_TXD") (class "Default")
      (node (ref "P9") (pin "24") (pinfunction "24_24") (pintype "passive"))
      (node (ref "U$5") (pin "9") (pinfunction "DRDY_9") (pintype "output"))
    )
    (net (code "76") (name "/UART2_RXD") (class "Default")
      (node (ref "P9") (pin "22") (pinfunction "22_22") (pintype "passive"))
    )
    (net (code "77") (name "/UART2_TXD") (class "Default")
      (node (ref "P9") (pin "21") (pinfunction "21_21") (pintype "passive"))
    )
    (net (code "78") (name "/UART3_CTSN") (class "Default")
      (node (ref "P8") (pin "36") (pinfunction "36_36") (pintype "passive"))
    )
    (net (code "79") (name "/UART3_RTSN") (class "Default")
      (node (ref "P8") (pin "34") (pinfunction "34_34") (pintype "passive"))
    )
    (net (code "80") (name "/UART4_CTSN") (class "Default")
      (node (ref "P8") (pin "35") (pinfunction "35_35") (pintype "passive"))
    )
    (net (code "81") (name "/UART4_RTSN") (class "Default")
      (node (ref "P8") (pin "33") (pinfunction "33_33") (pintype "passive"))
    )
    (net (code "82") (name "/UART4_RXD") (class "Default")
      (node (ref "P9") (pin "11") (pinfunction "11_11") (pintype "passive"))
    )
    (net (code "83") (name "/UART4_TXD") (class "Default")
      (node (ref "P9") (pin "13") (pinfunction "13_13") (pintype "passive"))
      (node (ref "U$5") (pin "5") (pinfunction "INT1_5") (pintype "output"))
    )
    (net (code "84") (name "/UART5_CTSN") (class "Default")
      (node (ref "P8") (pin "31") (pinfunction "31_31") (pintype "passive"))
    )
    (net (code "85") (name "/UART5_RTSN") (class "Default")
      (node (ref "P8") (pin "32") (pinfunction "32_32") (pintype "passive"))
    )
    (net (code "86") (name "/UART5_RXD") (class "Default")
      (node (ref "P8") (pin "38") (pinfunction "38_38") (pintype "passive"))
    )
    (net (code "87") (name "/UART5_TXD") (class "Default")
      (node (ref "P8") (pin "37") (pinfunction "37_37") (pintype "passive"))
    )
    (net (code "88") (name "1.5V") (class "Default")
      (node (ref "C22") (pin "1") (pinfunction "1_1") (pintype "passive"))
      (node (ref "C3") (pin "1") (pinfunction "1_1") (pintype "passive"))
      (node (ref "U$12") (pin "5") (pinfunction "OUT_5") (pintype "power_in"))
      (node (ref "U$3") (pin "6") (pinfunction "DVDD_6") (pintype "power_in"))
    )
    (net (code "89") (name "1.8V") (class "Default")
      (node (ref "P9") (pin "32") (pinfunction "32_32") (pintype "passive"))
    )
    (net (code "90") (name "2.8V") (class "Default")
      (node (ref "C19") (pin "1") (pinfunction "1_1") (pintype "passive"))
      (node (ref "C2") (pin "1") (pinfunction "1_1") (pintype "passive"))
      (node (ref "C23") (pin "1") (pinfunction "1_1") (pintype "passive"))
      (node (ref "C24") (pin "1") (pinfunction "1_1") (pintype "passive"))
      (node (ref "C27") (pin "1") (pinfunction "1_1") (pintype "passive"))
      (node (ref "U$10") (pin "5") (pinfunction "VOUT_5") (pintype "power_in"))
      (node (ref "U$13") (pin "18") (pinfunction "VCCB_18") (pintype "power_in"))
      (node (ref "U$13") (pin "7") (pinfunction "VCCB_7") (pintype "power_in"))
      (node (ref "U$3") (pin "11") (pinfunction "PVDD_11") (pintype "power_in"))
      (node (ref "U$3") (pin "16") (pinfunction "IOVDD_16") (pintype "power_in"))
      (node (ref "U$4") (pin "6") (pinfunction "VCCB_6") (pintype "power_in"))
    )
    (net (code "91") (name "AGND") (class "Default")
      (node (ref "P9") (pin "34") (pinfunction "34_34") (pintype "passive"))
    )
    (net (code "92") (name "GND") (class "Default")
      (node (ref "C1") (pin "2") (pinfunction "2_2") (pintype "passive"))
      (node (ref "C10") (pin "2") (pinfunction "2_2") (pintype "passive"))
      (node (ref "C13") (pin "2") (pinfunction "2_2") (pintype "passive"))
      (node (ref "C14") (pin "2") (pinfunction "2_2") (pintype "passive"))
      (node (ref "C15") (pin "2") (pinfunction "2_2") (pintype "passive"))
      (node (ref "C16") (pin "2") (pinfunction "2_2") (pintype "passive"))
      (node (ref "C17") (pin "2") (pinfunction "2_2") (pintype "passive"))
      (node (ref "C18") (pin "2") (pinfunction "2_2") (pintype "passive"))
      (node (ref "C19") (pin "2") (pinfunction "2_2") (pintype "passive"))
      (node (ref "C2") (pin "2") (pinfunction "2_2") (pintype "passive"))
      (node (ref "C20") (pin "2") (pinfunction "2_2") (pintype "passive"))
      (node (ref "C21") (pin "2") (pinfunction "2_2") (pintype "passive"))
      (node (ref "C22") (pin "2") (pinfunction "2_2") (pintype "passive"))
      (node (ref "C23") (pin "2") (pinfunction "2_2") (pintype "passive"))
      (node (ref "C24") (pin "2") (pinfunction "2_2") (pintype "passive"))
      (node (ref "C25") (pin "2") (pinfunction "2_2") (pintype "passive"))
      (node (ref "C26") (pin "2") (pinfunction "2_2") (pintype "passive"))
      (node (ref "C27") (pin "2") (pinfunction "2_2") (pintype "passive"))
      (node (ref "C28") (pin "2") (pinfunction "2_2") (pintype "passive"))
      (node (ref "C3") (pin "2") (pinfunction "2_2") (pintype "passive"))
      (node (ref "C4") (pin "2") (pinfunction "2_2") (pintype "passive"))
      (node (ref "C5") (pin "2") (pinfunction "2_2") (pintype "passive"))
      (node (ref "C6") (pin "2") (pinfunction "2_2") (pintype "passive"))
      (node (ref "C8") (pin "2") (pinfunction "2_2") (pintype "passive"))
      (node (ref "C9") (pin "2") (pinfunction "2_2") (pintype "passive"))
      (node (ref "H1") (pin "GND") (pinfunction "GND_GND") (pintype "passive"))
      (node (ref "H2") (pin "GND") (pinfunction "GND_GND") (pintype "passive"))
      (node (ref "H3") (pin "GND") (pinfunction "GND_GND") (pintype "passive"))
      (node (ref "H4") (pin "GND") (pinfunction "GND_GND") (pintype "passive"))
      (node (ref "P8") (pin "1") (pinfunction "1_1") (pintype "passive"))
      (node (ref "P8") (pin "2") (pinfunction "2_2") (pintype "passive"))
      (node (ref "P9") (pin "1") (pinfunction "1_1") (pintype "passive"))
      (node (ref "P9") (pin "2") (pinfunction "2_2") (pintype "passive"))
      (node (ref "P9") (pin "43") (pinfunction "43_43") (pintype "passive"))
      (node (ref "P9") (pin "44") (pinfunction "44_44") (pintype "passive"))
      (node (ref "P9") (pin "45") (pinfunction "45_45") (pintype "passive"))
      (node (ref "P9") (pin "46") (pinfunction "46_46") (pintype "passive"))
      (node (ref "R33") (pin "1") (pinfunction "1_1") (pintype "passive"))
      (node (ref "R34") (pin "1") (pinfunction "1_1") (pintype "passive"))
      (node (ref "R36") (pin "2") (pinfunction "2_2") (pintype "passive"))
      (node (ref "R4") (pin "1") (pinfunction "1_1") (pintype "passive"))
      (node (ref "S1") (pin "1") (pinfunction "1_1") (pintype "passive"))
      (node (ref "S1") (pin "2") (pinfunction "2_2") (pintype "passive"))
      (node (ref "U$1") (pin "4") (pinfunction "VSS_4") (pintype "power_in"))
      (node (ref "U$10") (pin "2") (pinfunction "GND_2") (pintype "power_in"))
      (node (ref "U$12") (pin "2") (pinfunction "GND_2") (pintype "power_in"))
      (node (ref "U$13") (pin "1") (pinfunction "1DIR_1") (pintype "input"))
      (node (ref "U$13") (pin "10") (pinfunction "GND_10") (pintype "power_in"))
      (node (ref "U$13") (pin "15") (pinfunction "GND_15") (pintype "power_in"))
      (node (ref "U$13") (pin "19") (pinfunction "2B5_19") (pintype "bidirectional"))
      (node (ref "U$13") (pin "20") (pinfunction "2B6_20") (pintype "bidirectional"))
      (node (ref "U$13") (pin "21") (pinfunction "GND_21") (pintype "power_in"))
      (node (ref "U$13") (pin "22") (pinfunction "2B7_22") (pintype "bidirectional"))
      (node (ref "U$13") (pin "23") (pinfunction "2B8_23") (pintype "bidirectional"))
      (node (ref "U$13") (pin "24") (pinfunction "2DIR_24") (pintype "input"))
      (node (ref "U$13") (pin "28") (pinfunction "GND_28") (pintype "power_in"))
      (node (ref "U$13") (pin "34") (pinfunction "GND_34") (pintype "power_in"))
      (node (ref "U$13") (pin "39") (pinfunction "GND_39") (pintype "power_in"))
      (node (ref "U$13") (pin "4") (pinfunction "GND_4") (pintype "power_in"))
      (node (ref "U$13") (pin "45") (pinfunction "GND_45") (pintype "power_in"))
      (node (ref "U$3") (pin "5") (pinfunction "IOVSS_5") (pintype "power_in"))
      (node (ref "U$3") (pin "7") (pinfunction "DVSS_7") (pintype "power_in"))
      (node (ref "U$4") (pin "2") (pinfunction "GND_2") (pintype "power_in"))
      (node (ref "U$5") (pin "10") (pinfunction "GND_10") (pintype "power_in"))
      (node (ref "U$5") (pin "11") (pinfunction "GND_11") (pintype "power_in"))
      (node (ref "U$5") (pin "7") (pinfunction "GND_7") (pintype "power_in"))
      (node (ref "U$7") (pin "1") (pinfunction "GND_1") (pintype "power_in"))
      (node (ref "U$7") (pin "2") (pinfunction "GND_2") (pintype "power_in"))
      (node (ref "U$7") (pin "27") (pinfunction "SD0_A/SA0_27") (pintype "bidirectional"))
      (node (ref "U$7") (pin "3") (pinfunction "GND_3") (pintype "power_in"))
      (node (ref "U$7") (pin "4") (pinfunction "GND_4") (pintype "power_in"))
      (node (ref "U$7") (pin "5") (pinfunction "GND_5") (pintype "power_in"))
      (node (ref "U$7") (pin "6") (pinfunction "GND_6") (pintype "power_in"))
      (node (ref "U$8") (pin "1") (pinfunction "GND_1") (pintype "power_in"))
      (node (ref "U$8") (pin "2") (pinfunction "GND_2") (pintype "power_in"))
      (node (ref "U$8") (pin "26") (pinfunction "SDO_G/SA0_26") (pintype "bidirectional"))
      (node (ref "U$8") (pin "3") (pinfunction "GND_3") (pintype "power_in"))
      (node (ref "U$8") (pin "4") (pinfunction "GND_4") (pintype "power_in"))
      (node (ref "U$8") (pin "6") (pinfunction "GND_6") (pintype "power_in"))
      (node (ref "U$8") (pin "7") (pinfunction "GND_7") (pintype "power_in"))
    )
    (net (code "93") (name "Net-(LED1-PadC)") (class "Default")
      (node (ref "LED1") (pin "C") (pinfunction "C_C") (pintype "passive"))
      (node (ref "R33") (pin "2") (pinfunction "2_2") (pintype "passive"))
    )
    (net (code "94") (name "Net-(LED2-PadC)") (class "Default")
      (node (ref "LED2") (pin "C") (pinfunction "C_C") (pintype "passive"))
      (node (ref "R34") (pin "2") (pinfunction "2_2") (pintype "passive"))
    )
    (net (code "95") (name "Net-(LED3-PadC)") (class "Default")
      (node (ref "LED3") (pin "C") (pinfunction "C_C") (pintype "passive"))
      (node (ref "R35") (pin "2") (pinfunction "2_2") (pintype "passive"))
    )
    (net (code "96") (name "Net-(U$1-A0)") (class "Default")
      (node (ref "R7") (pin "1") (pinfunction "1_1") (pintype "passive"))
      (node (ref "S1") (pin "4") (pinfunction "4_4") (pintype "passive"))
      (node (ref "U$1") (pin "1") (pinfunction "A0_1") (pintype "input"))
    )
    (net (code "97") (name "Net-(U$1-A1)") (class "Default")
      (node (ref "R2") (pin "1") (pinfunction "1_1") (pintype "passive"))
      (node (ref "S1") (pin "3") (pinfunction "3_3") (pintype "passive"))
      (node (ref "U$1") (pin "2") (pinfunction "A1_2") (pintype "input"))
    )
    (net (code "98") (name "Net-(U$1-A2)") (class "Default")
      (node (ref "R4") (pin "2") (pinfunction "2_2") (pintype "passive"))
      (node (ref "R5") (pin "1") (pinfunction "1_1") (pintype "passive"))
      (node (ref "U$1") (pin "3") (pinfunction "A2_3") (pintype "input"))
    )
    (net (code "99") (name "Net-(U$1-WP)") (class "Default")
      (node (ref "R9") (pin "1") (pinfunction "1_1") (pintype "passive"))
      (node (ref "TP1") (pin "TP") (pinfunction "TP_TP") (pintype "input"))
      (node (ref "U$1") (pin "7") (pinfunction "WP_7") (pintype "input"))
    )
    (net (code "100") (name "Net-(U$3-DCLK)") (class "Default")
      (node (ref "R19") (pin "2") (pinfunction "2_2") (pintype "passive"))
      (node (ref "U$3") (pin "10") (pinfunction "DCLK_10") (pintype "output"))
    )
    (net (code "101") (name "Net-(U$3-DOUT0)") (class "Default")
      (node (ref "R6") (pin "2") (pinfunction "2_2") (pintype "passive"))
      (node (ref "U$3") (pin "1") (pinfunction "DOUT0_1") (pintype "output"))
    )
    (net (code "102") (name "Net-(U$3-DOUT1)") (class "Default")
      (node (ref "R8") (pin "2") (pinfunction "2_2") (pintype "passive"))
      (node (ref "U$3") (pin "2") (pinfunction "DOUT1_2") (pintype "output"))
    )
    (net (code "103") (name "Net-(U$3-DOUT2)") (class "Default")
      (node (ref "R10") (pin "2") (pinfunction "2_2") (pintype "passive"))
      (node (ref "U$3") (pin "3") (pinfunction "DOUT2_3") (pintype "output"))
    )
    (net (code "104") (name "Net-(U$3-DOUT3)") (class "Default")
      (node (ref "R11") (pin "2") (pinfunction "2_2") (pintype "passive"))
      (node (ref "U$3") (pin "4") (pinfunction "DOUT3_4") (pintype "output"))
    )
    (net (code "105") (name "Net-(U$3-DOUT4)") (class "Default")
      (node (ref "R12") (pin "2") (pinfunction "2_2") (pintype "passive"))
      (node (ref "U$3") (pin "17") (pinfunction "DOUT4_17") (pintype "output"))
    )
    (net (code "106") (name "Net-(U$3-DOUT5)") (class "Default")
      (node (ref "R13") (pin "2") (pinfunction "2_2") (pintype "passive"))
      (node (ref "U$3") (pin "18") (pinfunction "DOUT5_18") (pintype "output"))
    )
    (net (code "107") (name "Net-(U$3-DOUT6)") (class "Default")
      (node (ref "R14") (pin "2") (pinfunction "2_2") (pintype "passive"))
      (node (ref "U$3") (pin "19") (pinfunction "DOUT6_19") (pintype "output"))
    )
    (net (code "108") (name "Net-(U$3-DOUT7)") (class "Default")
      (node (ref "R15") (pin "2") (pinfunction "2_2") (pintype "passive"))
      (node (ref "U$3") (pin "20") (pinfunction "DOUT7_20") (pintype "output"))
    )
    (net (code "109") (name "Net-(U$3-EXTCLK)") (class "Default")
      (node (ref "R38") (pin "1") (pinfunction "1_1") (pintype "passive"))
      (node (ref "U$3") (pin "12") (pinfunction "EXTCLK_12") (pintype "input"))
    )
    (net (code "110") (name "Net-(U$3-HD)") (class "Default")
      (node (ref "R17") (pin "2") (pinfunction "2_2") (pintype "passive"))
      (node (ref "U$3") (pin "9") (pinfunction "HD_9") (pintype "output"))
    )
    (net (code "111") (name "Net-(U$3-RESET)") (class "Default")
      (node (ref "R18") (pin "2") (pinfunction "2_2") (pintype "passive"))
      (node (ref "R36") (pin "1") (pinfunction "1_1") (pintype "passive"))
      (node (ref "U$3") (pin "13") (pinfunction "RESET_13") (pintype "input"))
    )
    (net (code "112") (name "Net-(U$3-VD)") (class "Default")
      (node (ref "R16") (pin "2") (pinfunction "2_2") (pintype "passive"))
      (node (ref "U$3") (pin "8") (pinfunction "VD_8") (pintype "output"))
    )
    (net (code "113") (name "Net-(U$4-A)") (class "Default")
      (node (ref "R37") (pin "2") (pinfunction "2_2") (pintype "passive"))
      (node (ref "U$4") (pin "3") (pinfunction "A_3") (pintype "bidirectional"))
    )
    (net (code "114") (name "Net-(U$4-B)") (class "Default")
      (node (ref "R38") (pin "2") (pinfunction "2_2") (pintype "passive"))
      (node (ref "U$4") (pin "4") (pinfunction "B_4") (pintype "bidirectional"))
    )
    (net (code "115") (name "Net-(U$5-C1)") (class "Default")
      (node (ref "C5") (pin "1") (pinfunction "1_1") (pintype "passive"))
      (node (ref "U$5") (pin "6") (pinfunction "C1_6") (pintype "passive"))
    )
    (net (code "116") (name "Net-(U$5-SETC)") (class "Default")
      (node (ref "C7") (pin "2") (pinfunction "2_2") (pintype "passive"))
      (node (ref "U$5") (pin "13") (pinfunction "SETC_13") (pintype "passive"))
    )
    (net (code "117") (name "Net-(U$5-SETP)") (class "Default")
      (node (ref "C7") (pin "1") (pinfunction "1_1") (pintype "passive"))
      (node (ref "U$5") (pin "12") (pinfunction "SETP_12") (pintype "passive"))
    )
    (net (code "118") (name "Net-(U$7-CAP)") (class "Default")
      (node (ref "C16") (pin "1") (pinfunction "1_1") (pintype "passive"))
      (node (ref "U$7") (pin "15") (pinfunction "CAP_15") (pintype "passive"))
    )
    (net (code "119") (name "Net-(U$8-C1)") (class "Default")
      (node (ref "C12") (pin "1") (pinfunction "1_1") (pintype "passive"))
      (node (ref "U$8") (pin "5") (pinfunction "C1_5") (pintype "passive"))
    )
    (net (code "120") (name "Net-(U$8-SETC)") (class "Default")
      (node (ref "C11") (pin "1") (pinfunction "1_1") (pintype "passive"))
      (node (ref "U$8") (pin "13") (pinfunction "SETC_13") (pintype "passive"))
    )
    (net (code "121") (name "Net-(U$8-SETP)") (class "Default")
      (node (ref "C11") (pin "2") (pinfunction "2_2") (pintype "passive"))
      (node (ref "C12") (pin "2") (pinfunction "2_2") (pintype "passive"))
      (node (ref "U$8") (pin "14") (pinfunction "SETP_14") (pintype "passive"))
    )
    (net (code "122") (name "Net-(U$10-BYPASS)") (class "Default")
      (node (ref "C18") (pin "1") (pinfunction "1_1") (pintype "passive"))
      (node (ref "U$10") (pin "4") (pinfunction "BYPASS_4") (pintype "passive"))
    )
    (net (code "123") (name "Net-(U$12-NR)") (class "Default")
      (node (ref "C21") (pin "1") (pinfunction "1_1") (pintype "passive"))
      (node (ref "U$12") (pin "4") (pinfunction "NR_4") (pintype "passive"))
    )
    (net (code "124") (name "Net-(U$13-1A1)") (class "Default")
      (node (ref "R20") (pin "2") (pinfunction "2_2") (pintype "passive"))
      (node (ref "U$13") (pin "47") (pinfunction "1A1_47") (pintype "bidirectional"))
    )
    (net (code "125") (name "Net-(U$13-1A2)") (class "Default")
      (node (ref "R21") (pin "2") (pinfunction "2_2") (pintype "passive"))
      (node (ref "U$13") (pin "46") (pinfunction "1A2_46") (pintype "bidirectional"))
    )
    (net (code "126") (name "Net-(U$13-1A3)") (class "Default")
      (node (ref "R22") (pin "2") (pinfunction "2_2") (pintype "passive"))
      (node (ref "U$13") (pin "44") (pinfunction "1A3_44") (pintype "bidirectional"))
    )
    (net (code "127") (name "Net-(U$13-1A4)") (class "Default")
      (node (ref "R23") (pin "2") (pinfunction "2_2") (pintype "passive"))
      (node (ref "U$13") (pin "43") (pinfunction "1A4_43") (pintype "bidirectional"))
    )
    (net (code "128") (name "Net-(U$13-1A5)") (class "Default")
      (node (ref "R24") (pin "2") (pinfunction "2_2") (pintype "passive"))
      (node (ref "U$13") (pin "41") (pinfunction "1A5_41") (pintype "bidirectional"))
    )
    (net (code "129") (name "Net-(U$13-1A6)") (class "Default")
      (node (ref "R25") (pin "2") (pinfunction "2_2") (pintype "passive"))
      (node (ref "U$13") (pin "40") (pinfunction "1A6_40") (pintype "bidirectional"))
    )
    (net (code "130") (name "Net-(U$13-1A7)") (class "Default")
      (node (ref "R26") (pin "2") (pinfunction "2_2") (pintype "passive"))
      (node (ref "U$13") (pin "38") (pinfunction "1A7_38") (pintype "bidirectional"))
    )
    (net (code "131") (name "Net-(U$13-1A8)") (class "Default")
      (node (ref "R27") (pin "2") (pinfunction "2_2") (pintype "passive"))
      (node (ref "U$13") (pin "37") (pinfunction "1A8_37") (pintype "bidirectional"))
    )
    (net (code "132") (name "Net-(U$13-1B1)") (class "Default")
      (node (ref "R6") (pin "1") (pinfunction "1_1") (pintype "passive"))
      (node (ref "U$13") (pin "2") (pinfunction "1B1_2") (pintype "bidirectional"))
    )
    (net (code "133") (name "Net-(U$13-1B2)") (class "Default")
      (node (ref "R8") (pin "1") (pinfunction "1_1") (pintype "passive"))
      (node (ref "U$13") (pin "3") (pinfunction "1B2_3") (pintype "bidirectional"))
    )
    (net (code "134") (name "Net-(U$13-1B3)") (class "Default")
      (node (ref "R10") (pin "1") (pinfunction "1_1") (pintype "passive"))
      (node (ref "U$13") (pin "5") (pinfunction "1B3_5") (pintype "bidirectional"))
    )
    (net (code "135") (name "Net-(U$13-1B4)") (class "Default")
      (node (ref "R11") (pin "1") (pinfunction "1_1") (pintype "passive"))
      (node (ref "U$13") (pin "6") (pinfunction "1B4_6") (pintype "bidirectional"))
    )
    (net (code "136") (name "Net-(U$13-1B5)") (class "Default")
      (node (ref "R12") (pin "1") (pinfunction "1_1") (pintype "passive"))
      (node (ref "U$13") (pin "8") (pinfunction "1B5_8") (pintype "bidirectional"))
    )
    (net (code "137") (name "Net-(U$13-1B6)") (class "Default")
      (node (ref "R13") (pin "1") (pinfunction "1_1") (pintype "passive"))
      (node (ref "U$13") (pin "9") (pinfunction "1B6_9") (pintype "bidirectional"))
    )
    (net (code "138") (name "Net-(U$13-1B7)") (class "Default")
      (node (ref "R14") (pin "1") (pinfunction "1_1") (pintype "passive"))
      (node (ref "U$13") (pin "11") (pinfunction "1B7_11") (pintype "bidirectional"))
    )
    (net (code "139") (name "Net-(U$13-1B8)") (class "Default")
      (node (ref "R15") (pin "1") (pinfunction "1_1") (pintype "passive"))
      (node (ref "U$13") (pin "12") (pinfunction "1B8_12") (pintype "bidirectional"))
    )
    (net (code "140") (name "Net-(U$13-2A1)") (class "Default")
      (node (ref "R28") (pin "2") (pinfunction "2_2") (pintype "passive"))
      (node (ref "U$13") (pin "36") (pinfunction "2A1_36") (pintype "bidirectional"))
    )
    (net (code "141") (name "Net-(U$13-2A2)") (class "Default")
      (node (ref "R29") (pin "2") (pinfunction "2_2") (pintype "passive"))
      (node (ref "U$13") (pin "35") (pinfunction "2A2_35") (pintype "bidirectional"))
    )
    (net (code "142") (name "Net-(U$13-2A3)") (class "Default")
      (node (ref "R30") (pin "2") (pinfunction "2_2") (pintype "passive"))
      (node (ref "U$13") (pin "33") (pinfunction "2A3_33") (pintype "bidirectional"))
    )
    (net (code "143") (name "Net-(U$13-2A4)") (class "Default")
      (node (ref "R31") (pin "2") (pinfunction "2_2") (pintype "passive"))
      (node (ref "U$13") (pin "32") (pinfunction "2A4_32") (pintype "bidirectional"))
    )
    (net (code "144") (name "Net-(U$13-2B1)") (class "Default")
      (node (ref "R16") (pin "1") (pinfunction "1_1") (pintype "passive"))
      (node (ref "U$13") (pin "13") (pinfunction "2B1_13") (pintype "bidirectional"))
    )
    (net (code "145") (name "Net-(U$13-2B2)") (class "Default")
      (node (ref "R17") (pin "1") (pinfunction "1_1") (pintype "passive"))
      (node (ref "U$13") (pin "14") (pinfunction "2B2_14") (pintype "bidirectional"))
    )
    (net (code "146") (name "Net-(U$13-2B3)") (class "Default")
      (node (ref "R18") (pin "1") (pinfunction "1_1") (pintype "passive"))
      (node (ref "U$13") (pin "16") (pinfunction "2B3_16") (pintype "bidirectional"))
    )
    (net (code "147") (name "Net-(U$13-2B4)") (class "Default")
      (node (ref "R19") (pin "1") (pinfunction "1_1") (pintype "passive"))
      (node (ref "U$13") (pin "17") (pinfunction "2B4_17") (pintype "bidirectional"))
    )
    (net (code "148") (name "VDD") (class "Default")
      (node (ref "P9") (pin "5") (pinfunction "5_5") (pintype "passive"))
      (node (ref "P9") (pin "6") (pinfunction "6_6") (pintype "passive"))
    )
    (net (code "149") (name "unconnected-(U$5-INT2-Pad4)") (class "Default")
      (node (ref "U$5") (pin "4") (pinfunction "INT2_4") (pintype "output"))
    )
    (net (code "150") (name "unconnected-(U$7-DRDY_G{slash}INT2_G-Pad17)") (class "Default")
      (node (ref "U$7") (pin "17") (pinfunction "DRDY_G/INT2_G_17") (pintype "output"))
    )
    (net (code "151") (name "unconnected-(U$7-INT2_A-Pad19)") (class "Default")
      (node (ref "U$7") (pin "19") (pinfunction "INT2_A_19") (pintype "output"))
    )
    (net (code "152") (name "unconnected-(U$8-DRDY_G{slash}INT2_G-Pad18)") (class "Default")
      (node (ref "U$8") (pin "18") (pinfunction "DRDY_G/INT2_G_18") (pintype "output"))
    )
    (net (code "153") (name "unconnected-(U$8-INT2_A{slash}M-Pad19)") (class "Default")
      (node (ref "U$8") (pin "19") (pinfunction "INT2_A/M_19") (pintype "output"))
    )
    (net (code "154") (name "unconnected-(U$13-2A5-Pad30)") (class "Default")
      (node (ref "U$13") (pin "30") (pinfunction "2A5_30") (pintype "bidirectional"))
    )
    (net (code "155") (name "unconnected-(U$13-2A6-Pad29)") (class "Default")
      (node (ref "U$13") (pin "29") (pinfunction "2A6_29") (pintype "bidirectional"))
    )
    (net (code "156") (name "unconnected-(U$13-2A7-Pad27)") (class "Default")
      (node (ref "U$13") (pin "27") (pinfunction "2A7_27") (pintype "bidirectional"))
    )
    (net (code "157") (name "unconnected-(U$13-2A8-Pad26)") (class "Default")
      (node (ref "U$13") (pin "26") (pinfunction "2A8_26") (pintype "bidirectional"))
    )
  )
)
